# School_System_Wiring.net
KiCad netlist of a schematic drawn in EAGLE
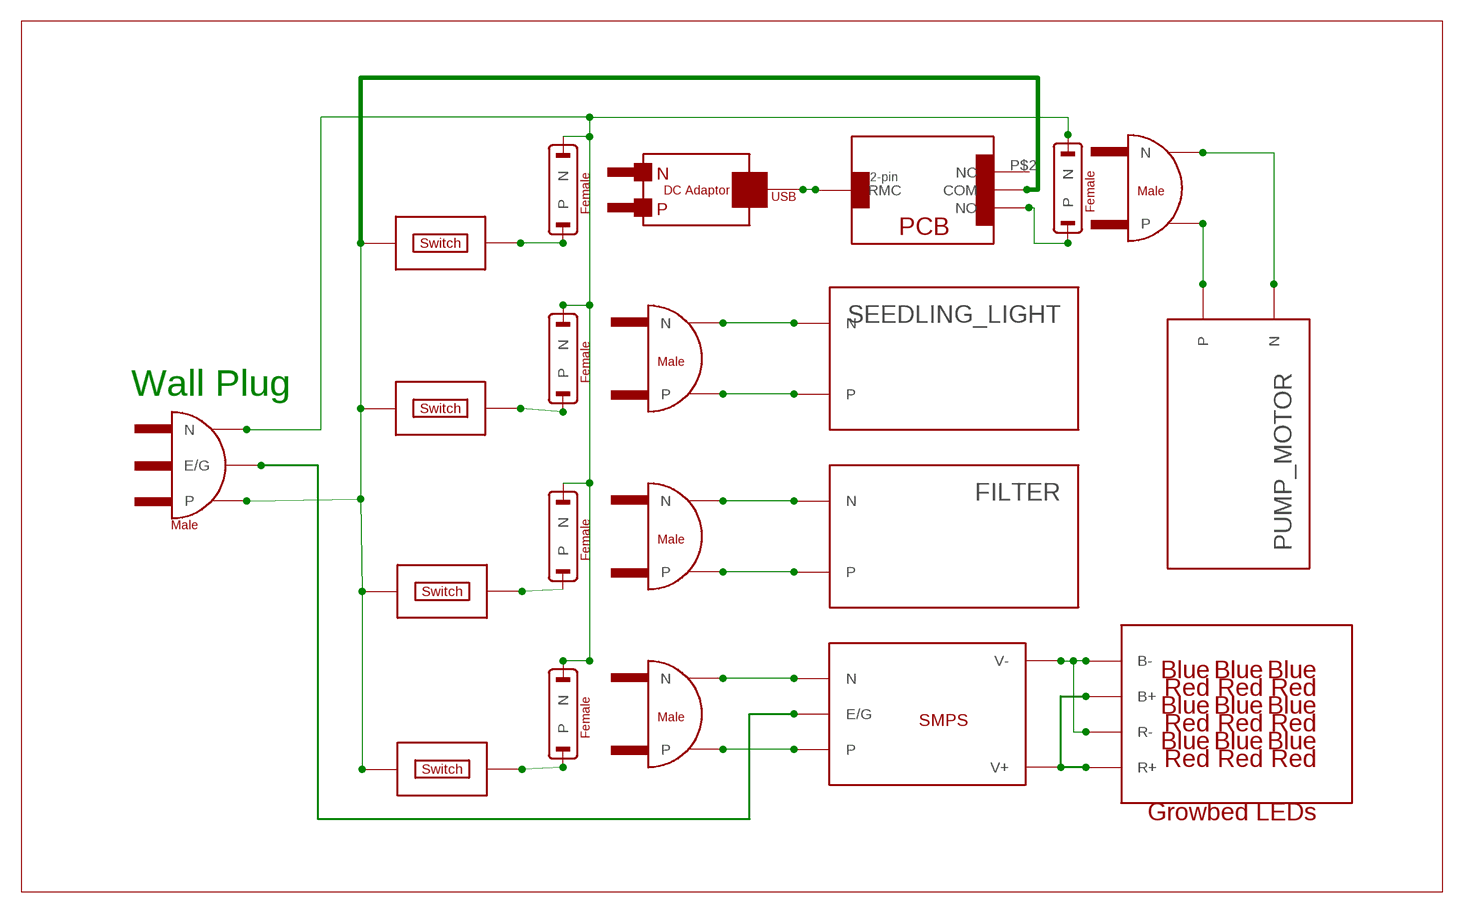
[diagram p0: schematic, sheet 1]

(export (version "E")
  (design (tool "Eeschema 10.0.6"))
  (components
    (comp (ref "FILTER")
      (value "EQUIPMENT")
      (footprint "eagle-import:2PINS")
      (libsource (lib "eagle-import") (part "EQUIPMENT"))
    )
    (comp (ref "PUMP_MOTOR")
      (value "EQUIPMENT")
      (footprint "eagle-import:2PINS")
      (libsource (lib "eagle-import") (part "EQUIPMENT"))
    )
    (comp (ref "SEEDLING_LIGHT")
      (value "EQUIPMENT")
      (footprint "eagle-import:2PINS")
      (libsource (lib "eagle-import") (part "EQUIPMENT"))
    )
    (comp (ref "U$1")
      (value "AC-PLUG-3")
      (footprint "eagle-import:3PINS")
      (libsource (lib "eagle-import") (part "AC-PLUG-3"))
    )
    (comp (ref "U$2")
      (value "AC-PLUG-2")
      (footprint "eagle-import:2PINS")
      (libsource (lib "eagle-import") (part "AC-PLUG-2"))
    )
    (comp (ref "U$3")
      (value "AC-PLUG-2")
      (footprint "eagle-import:2PINS")
      (libsource (lib "eagle-import") (part "AC-PLUG-2"))
    )
    (comp (ref "U$4")
      (value "AC-PLUG-2")
      (footprint "eagle-import:2PINS")
      (libsource (lib "eagle-import") (part "AC-PLUG-2"))
    )
    (comp (ref "U$5")
      (value "AC-PLUG-2")
      (footprint "eagle-import:2PINS")
      (libsource (lib "eagle-import") (part "AC-PLUG-2"))
    )
    (comp (ref "U$6")
      (value "DC_ADAPTOR")
      (footprint "eagle-import:1PIN")
      (libsource (lib "eagle-import") (part "DC_ADAPTOR"))
    )
    (comp (ref "U$7")
      (value "SCHOOL_PCB")
      (footprint "eagle-import:4PINS")
      (libsource (lib "eagle-import") (part "SCHOOL_PCB"))
    )
    (comp (ref "U$10")
      (value "GROWBED_LEDS")
      (footprint "eagle-import:4PINS")
      (libsource (lib "eagle-import") (part "GROWBED_LEDS"))
    )
    (comp (ref "U$11")
      (value "SWITCH")
      (footprint "eagle-import:2PINS")
      (libsource (lib "eagle-import") (part "SWITCH"))
    )
    (comp (ref "U$12")
      (value "SWITCH")
      (footprint "eagle-import:2PINS")
      (libsource (lib "eagle-import") (part "SWITCH"))
    )
    (comp (ref "U$13")
      (value "SWITCH")
      (footprint "eagle-import:2PINS")
      (libsource (lib "eagle-import") (part "SWITCH"))
    )
    (comp (ref "U$14")
      (value "SWITCH")
      (footprint "eagle-import:2PINS")
      (libsource (lib "eagle-import") (part "SWITCH"))
    )
    (comp (ref "U$15")
      (value "SMPS")
      (footprint "eagle-import:5PINS")
      (libsource (lib "eagle-import") (part "SMPS"))
    )
    (comp (ref "X1")
      (value "AC-JACK-2")
      (footprint "eagle-import:2PINS")
      (libsource (lib "eagle-import") (part "AC-JACK-2"))
    )
    (comp (ref "X2")
      (value "AC-JACK-2")
      (footprint "eagle-import:2PINS")
      (libsource (lib "eagle-import") (part "AC-JACK-2"))
    )
    (comp (ref "X3")
      (value "AC-JACK-2")
      (footprint "eagle-import:2PINS")
      (libsource (lib "eagle-import") (part "AC-JACK-2"))
    )
    (comp (ref "X4")
      (value "AC-JACK-2")
      (footprint "eagle-import:2PINS")
      (libsource (lib "eagle-import") (part "AC-JACK-2"))
    )
    (comp (ref "X5")
      (value "AC-JACK-2")
      (footprint "eagle-import:2PINS")
      (libsource (lib "eagle-import") (part "AC-JACK-2"))
    )
  )
  (nets
    (net (code "1") (name "Net-(FILTER-N)") (class "Default")
      (node (ref "FILTER") (pin "2") (pinfunction "N_2") (pintype "bidirectional"))
      (node (ref "U$2") (pin "2") (pinfunction "N_2") (pintype "bidirectional"))
    )
    (net (code "2") (name "Net-(FILTER-P)") (class "Default")
      (node (ref "FILTER") (pin "1") (pinfunction "P_1") (pintype "bidirectional"))
      (node (ref "U$2") (pin "1") (pinfunction "P_1") (pintype "bidirectional"))
    )
    (net (code "3") (name "Net-(PUMP_MOTOR-N)") (class "Default")
      (node (ref "PUMP_MOTOR") (pin "2") (pinfunction "N_2") (pintype "bidirectional"))
      (node (ref "U$4") (pin "2") (pinfunction "N_2") (pintype "bidirectional"))
    )
    (net (code "4") (name "Net-(PUMP_MOTOR-P)") (class "Default")
      (node (ref "PUMP_MOTOR") (pin "1") (pinfunction "P_1") (pintype "bidirectional"))
      (node (ref "U$4") (pin "1") (pinfunction "P_1") (pintype "bidirectional"))
    )
    (net (code "5") (name "Net-(SEEDLING_LIGHT-N)") (class "Default")
      (node (ref "SEEDLING_LIGHT") (pin "2") (pinfunction "N_2") (pintype "bidirectional"))
      (node (ref "U$5") (pin "2") (pinfunction "N_2") (pintype "bidirectional"))
    )
    (net (code "6") (name "Net-(SEEDLING_LIGHT-P)") (class "Default")
      (node (ref "SEEDLING_LIGHT") (pin "1") (pinfunction "P_1") (pintype "bidirectional"))
      (node (ref "U$5") (pin "1") (pinfunction "P_1") (pintype "bidirectional"))
    )
    (net (code "7") (name "Net-(U$1-N)") (class "Default")
      (node (ref "U$1") (pin "3") (pinfunction "N_3") (pintype "bidirectional"))
      (node (ref "X1") (pin "2") (pinfunction "N_2") (pintype "bidirectional"))
      (node (ref "X2") (pin "2") (pinfunction "N_2") (pintype "bidirectional"))
      (node (ref "X3") (pin "2") (pinfunction "N_2") (pintype "bidirectional"))
      (node (ref "X4") (pin "2") (pinfunction "N_2") (pintype "bidirectional"))
      (node (ref "X5") (pin "2") (pinfunction "N_2") (pintype "bidirectional"))
    )
    (net (code "8") (name "Net-(U$1-P)") (class "Default")
      (node (ref "U$1") (pin "2") (pinfunction "P_2") (pintype "bidirectional"))
      (node (ref "U$11") (pin "1") (pinfunction "P$1_1") (pintype "bidirectional"))
      (node (ref "U$12") (pin "1") (pinfunction "P$1_1") (pintype "bidirectional"))
      (node (ref "U$13") (pin "1") (pinfunction "P$1_1") (pintype "bidirectional"))
      (node (ref "U$14") (pin "1") (pinfunction "P$1_1") (pintype "bidirectional"))
    )
    (net (code "9") (name "Net-(U$10-B+)") (class "Default")
      (node (ref "U$10") (pin "P$1") (pinfunction "B+_P$1") (pintype "bidirectional"))
      (node (ref "U$10") (pin "P$3") (pinfunction "R+_P$3") (pintype "bidirectional"))
      (node (ref "U$15") (pin "P$4") (pinfunction "V+_P$4") (pintype "bidirectional"))
    )
    (net (code "10") (name "Net-(U$10-B-)") (class "Default")
      (node (ref "U$10") (pin "P$2") (pinfunction "B-_P$2") (pintype "bidirectional"))
      (node (ref "U$10") (pin "P$4") (pinfunction "R-_P$4") (pintype "bidirectional"))
      (node (ref "U$15") (pin "P$5") (pinfunction "V-_P$5") (pintype "bidirectional"))
    )
    (net (code "11") (name "Net-(U$11-P$2)") (class "Default")
      (node (ref "U$11") (pin "2") (pinfunction "P$2_2") (pintype "bidirectional"))
      (node (ref "X1") (pin "1") (pinfunction "P_1") (pintype "bidirectional"))
    )
    (net (code "12") (name "Net-(U$12-P$2)") (class "Default")
      (node (ref "U$12") (pin "2") (pinfunction "P$2_2") (pintype "bidirectional"))
      (node (ref "X3") (pin "1") (pinfunction "P_1") (pintype "bidirectional"))
    )
    (net (code "13") (name "Net-(U$13-P$2)") (class "Default")
      (node (ref "U$13") (pin "2") (pinfunction "P$2_2") (pintype "bidirectional"))
      (node (ref "X2") (pin "1") (pinfunction "P_1") (pintype "bidirectional"))
    )
    (net (code "14") (name "Net-(U$14-P$2)") (class "Default")
      (node (ref "U$14") (pin "2") (pinfunction "P$2_2") (pintype "bidirectional"))
      (node (ref "X4") (pin "1") (pinfunction "P_1") (pintype "bidirectional"))
    )
    (net (code "15") (name "Net-(U$15-N)") (class "Default")
      (node (ref "U$15") (pin "P$2") (pinfunction "N_P$2") (pintype "bidirectional"))
      (node (ref "U$3") (pin "2") (pinfunction "N_2") (pintype "bidirectional"))
    )
    (net (code "16") (name "Net-(U$15-P)") (class "Default")
      (node (ref "U$15") (pin "P$3") (pinfunction "P_P$3") (pintype "bidirectional"))
      (node (ref "U$3") (pin "1") (pinfunction "P_1") (pintype "bidirectional"))
    )
    (net (code "17") (name "unconnected-(U$1-E{slash}G-Pad1)") (class "Default")
      (node (ref "U$1") (pin "1") (pinfunction "E/G_1") (pintype "bidirectional"))
    )
    (net (code "18") (name "unconnected-(U$6-P$3-PadP$1)") (class "Default")
      (node (ref "U$6") (pin "P$1") (pinfunction "P$3_P$1") (pintype "output"))
    )
    (net (code "19") (name "unconnected-(U$7-COM-PadP$3)") (class "Default")
      (node (ref "U$7") (pin "P$3") (pinfunction "COM_P$3") (pintype "bidirectional"))
    )
    (net (code "20") (name "unconnected-(U$7-NC-PadP$2)") (class "Default")
      (node (ref "U$7") (pin "P$2") (pinfunction "NC_P$2") (pintype "bidirectional"))
    )
    (net (code "21") (name "unconnected-(U$7-NO-PadP$4)") (class "Default")
      (node (ref "U$7") (pin "P$4") (pinfunction "NO_P$4") (pintype "bidirectional"))
    )
    (net (code "22") (name "unconnected-(U$7-RMC-PadP$1)") (class "Default")
      (node (ref "U$7") (pin "P$1") (pinfunction "RMC_P$1") (pintype "bidirectional"))
    )
    (net (code "23") (name "unconnected-(U$15-E{slash}G-PadP$1)") (class "Default")
      (node (ref "U$15") (pin "P$1") (pinfunction "E/G_P$1") (pintype "bidirectional"))
    )
    (net (code "24") (name "unconnected-(X5-P-Pad1)") (class "Default")
      (node (ref "X5") (pin "1") (pinfunction "P_1") (pintype "bidirectional"))
    )
  )
)
